# rc2014_8255.net
KiCad netlist of a schematic drawn in EAGLE
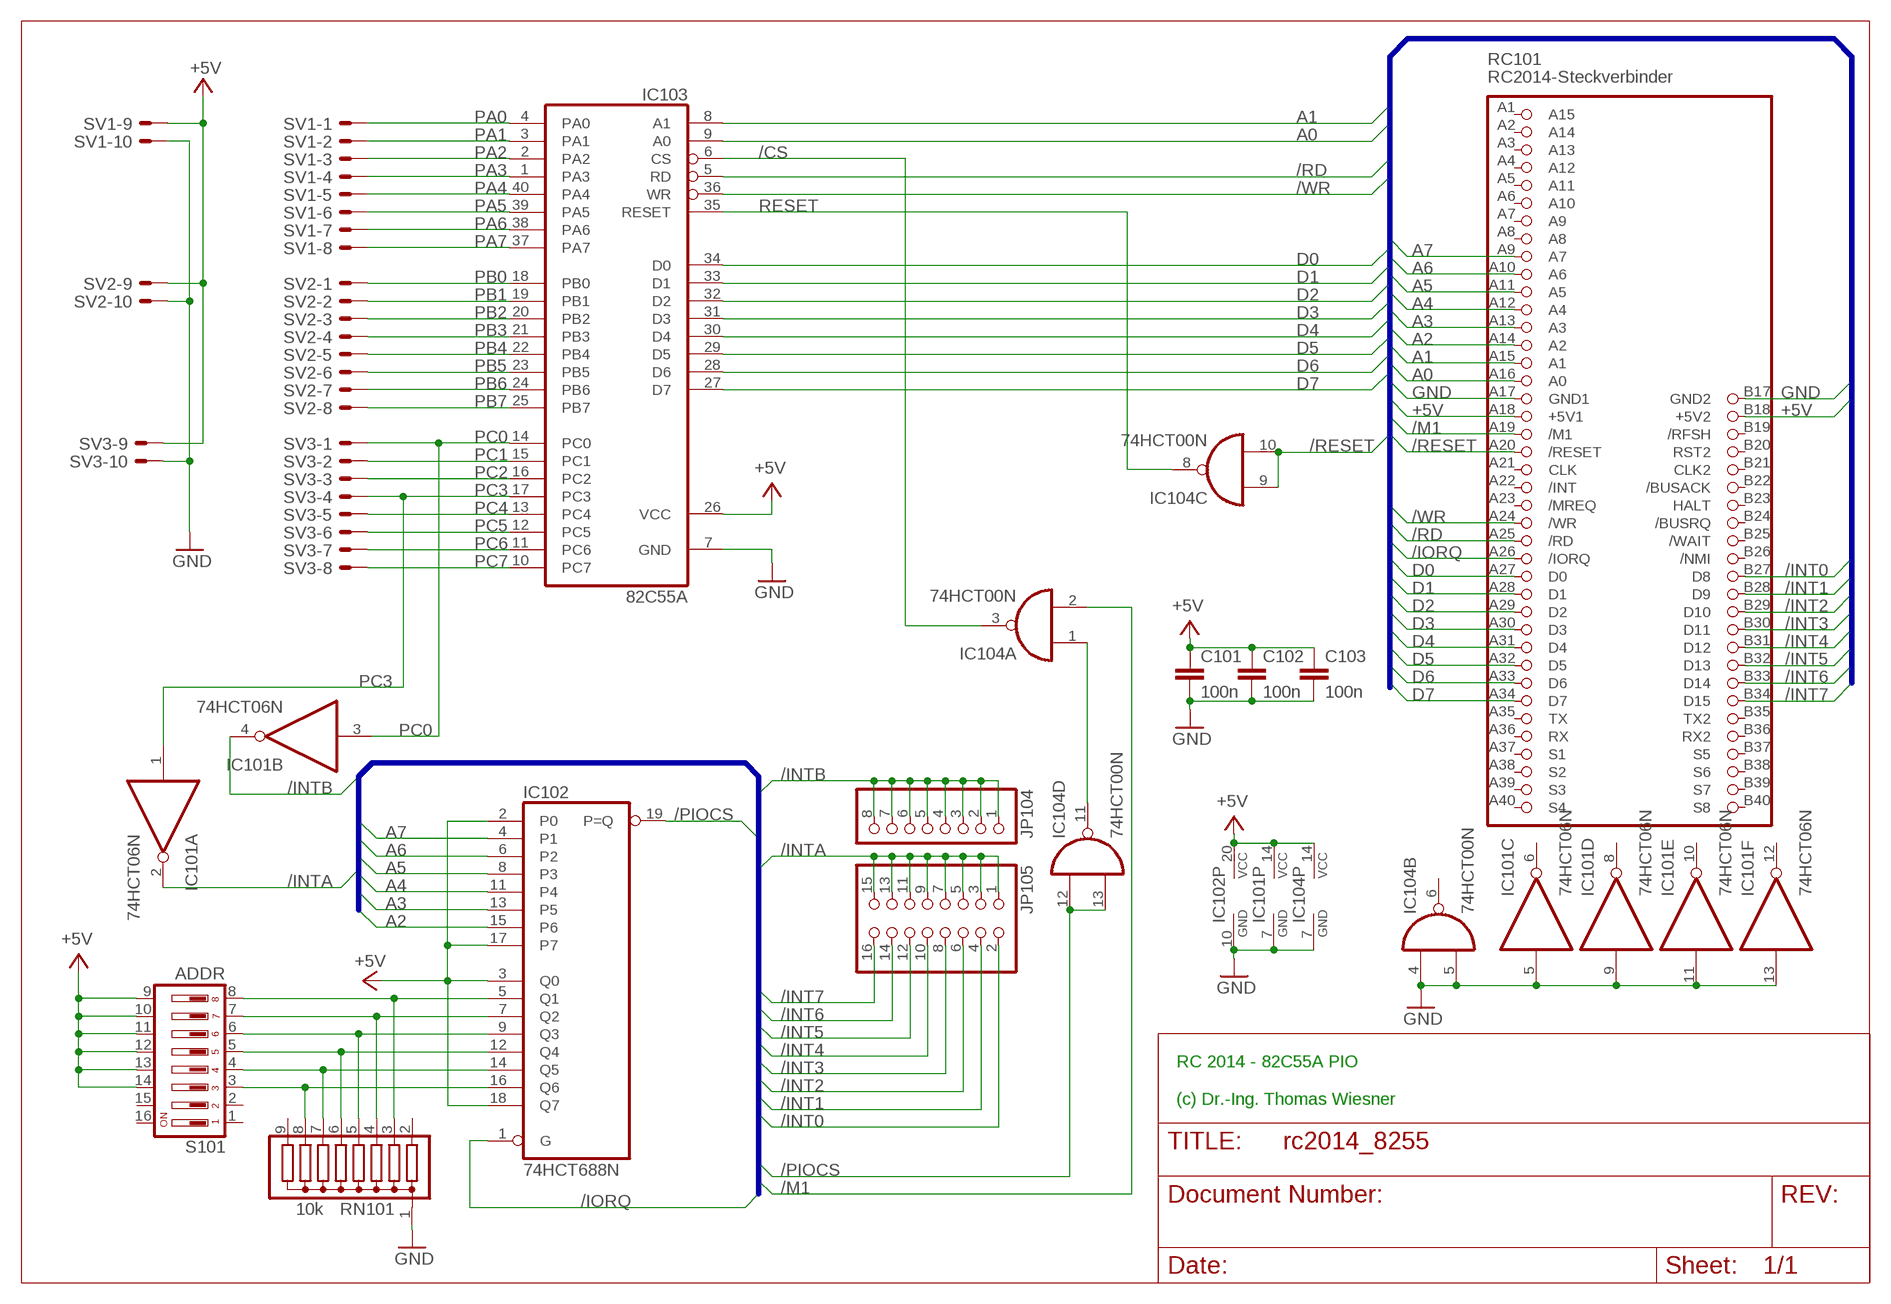
[diagram p0: schematic, sheet 1]

(export (version "E")
  (design (tool "Eeschema 10.0.6"))
  (components
    (comp (ref "C101")
      (value "100n")
      (footprint "eagle-import:C025-025X050")
      (libsource (lib "eagle-import") (part "C-EU025-025X050"))
    )
    (comp (ref "C102")
      (value "100n")
      (footprint "eagle-import:C025-025X050")
      (libsource (lib "eagle-import") (part "C-EU025-025X050"))
    )
    (comp (ref "C103")
      (value "100n")
      (footprint "eagle-import:C025-025X050")
      (libsource (lib "eagle-import") (part "C-EU025-025X050"))
    )
    (comp (ref "IC101")
      (value "74HCT06N")
      (footprint "eagle-import:DIL14")
      (libsource (lib "eagle-import") (part "7406NLS"))
    )
    (comp (ref "IC102")
      (value "74HCT688N")
      (footprint "eagle-import:DIL20")
      (libsource (lib "eagle-import") (part "74688NHCT"))
    )
    (comp (ref "IC103")
      (value "82C55A")
      (footprint "eagle-import:DIL40")
      (fields (field (name "MF") "INTERSIL") (field (name "MPN") "IP82C55AZ"))
      (libsource (lib "eagle-import") (part "82C55A"))
    )
    (comp (ref "IC104")
      (value "74HCT00N")
      (footprint "eagle-import:DIL14")
      (libsource (lib "eagle-import") (part "7400NLS"))
    )
    (comp (ref "JP104")
      (value "PINHD-1X8")
      (footprint "eagle-import:1X08")
      (libsource (lib "eagle-import") (part "PINHD-1X8"))
    )
    (comp (ref "JP105")
      (value "PINHD-2X8")
      (footprint "eagle-import:2X08")
      (libsource (lib "eagle-import") (part "PINHD-2X8"))
    )
    (comp (ref "RC101")
      (value "RC2014-Steckverbinder")
      (footprint "eagle-import:RC2014-STECKER")
      (libsource (lib "eagle-import") (part "RC2014STECKER"))
    )
    (comp (ref "RN101")
      (value "10k")
      (footprint "eagle-import:SIL9")
      (libsource (lib "eagle-import") (part "G08R"))
    )
    (comp (ref "S101")
      (value "ADDR")
      (footprint "eagle-import:DS-08")
      (fields (field (name "MPN") "DS08"))
      (libsource (lib "eagle-import") (part "DS08"))
    )
    (comp (ref "SV1")
      (value "ML10LE")
      (footprint "eagle-import:ML10L")
      (libsource (lib "eagle-import") (part "ML10LE"))
    )
    (comp (ref "SV2")
      (value "ML10LE")
      (footprint "eagle-import:ML10L")
      (libsource (lib "eagle-import") (part "ML10LE"))
    )
    (comp (ref "SV3")
      (value "ML10LE")
      (footprint "eagle-import:ML10L")
      (libsource (lib "eagle-import") (part "ML10LE"))
    )
  )
  (nets
    (net (code "2") (name "+5V") (class "Default")
      (node (ref "C101") (pin "1") (pinfunction "1_1") (pintype "passive"))
      (node (ref "C102") (pin "1") (pinfunction "1_1") (pintype "passive"))
      (node (ref "C103") (pin "1") (pinfunction "1_1") (pintype "passive"))
      (node (ref "IC101") (pin "14") (pinfunction "VCC_14") (pintype "power_in"))
      (node (ref "IC102") (pin "17") (pinfunction "P7_17") (pintype "input"))
      (node (ref "IC102") (pin "18") (pinfunction "Q7_18") (pintype "input"))
      (node (ref "IC102") (pin "2") (pinfunction "P0_2") (pintype "input"))
      (node (ref "IC102") (pin "20") (pinfunction "VCC_20") (pintype "power_in"))
      (node (ref "IC102") (pin "3") (pinfunction "Q0_3") (pintype "input"))
      (node (ref "IC103") (pin "26") (pinfunction "VCC_26") (pintype "power_in"))
      (node (ref "IC104") (pin "14") (pinfunction "VCC_14") (pintype "power_in"))
      (node (ref "RC101") (pin "A18") (pinfunction "+5V1_A18") (pintype "passive"))
      (node (ref "RC101") (pin "B18") (pinfunction "+5V2_B18") (pintype "passive"))
      (node (ref "S101") (pin "10") (pinfunction "10_10") (pintype "passive"))
      (node (ref "S101") (pin "11") (pinfunction "11_11") (pintype "passive"))
      (node (ref "S101") (pin "12") (pinfunction "12_12") (pintype "passive"))
      (node (ref "S101") (pin "13") (pinfunction "13_13") (pintype "passive"))
      (node (ref "S101") (pin "14") (pinfunction "14_14") (pintype "passive"))
      (node (ref "S101") (pin "9") (pinfunction "9_9") (pintype "passive"))
      (node (ref "SV1") (pin "9") (pinfunction "S_9") (pintype "passive"))
      (node (ref "SV2") (pin "9") (pinfunction "S_9") (pintype "passive"))
      (node (ref "SV3") (pin "9") (pinfunction "S_9") (pintype "passive"))
    )
    (net (code "4") (name "A0") (class "Default")
      (node (ref "IC103") (pin "9") (pinfunction "A0_9") (pintype "input"))
      (node (ref "RC101") (pin "A16") (pinfunction "A0_A16") (pintype "passive"))
    )
    (net (code "5") (name "A1") (class "Default")
      (node (ref "IC103") (pin "8") (pinfunction "A1_8") (pintype "input"))
      (node (ref "RC101") (pin "A15") (pinfunction "A1_A15") (pintype "passive"))
    )
    (net (code "6") (name "A2") (class "Default")
      (node (ref "IC102") (pin "15") (pinfunction "P6_15") (pintype "input"))
      (node (ref "RC101") (pin "A14") (pinfunction "A2_A14") (pintype "passive"))
    )
    (net (code "7") (name "A3") (class "Default")
      (node (ref "IC102") (pin "13") (pinfunction "P5_13") (pintype "input"))
      (node (ref "RC101") (pin "A13") (pinfunction "A3_A13") (pintype "passive"))
    )
    (net (code "8") (name "A4") (class "Default")
      (node (ref "IC102") (pin "11") (pinfunction "P4_11") (pintype "input"))
      (node (ref "RC101") (pin "A12") (pinfunction "A4_A12") (pintype "passive"))
    )
    (net (code "9") (name "A5") (class "Default")
      (node (ref "IC102") (pin "8") (pinfunction "P3_8") (pintype "input"))
      (node (ref "RC101") (pin "A11") (pinfunction "A5_A11") (pintype "passive"))
    )
    (net (code "10") (name "A6") (class "Default")
      (node (ref "IC102") (pin "6") (pinfunction "P2_6") (pintype "input"))
      (node (ref "RC101") (pin "A10") (pinfunction "A6_A10") (pintype "passive"))
    )
    (net (code "11") (name "A7") (class "Default")
      (node (ref "IC102") (pin "4") (pinfunction "P1_4") (pintype "input"))
      (node (ref "RC101") (pin "A9") (pinfunction "A7_A9") (pintype "passive"))
    )
    (net (code "12") (name "D0") (class "Default")
      (node (ref "IC103") (pin "34") (pinfunction "D0_34") (pintype "bidirectional"))
      (node (ref "RC101") (pin "A27") (pinfunction "D0_A27") (pintype "passive"))
    )
    (net (code "13") (name "D1") (class "Default")
      (node (ref "IC103") (pin "33") (pinfunction "D1_33") (pintype "bidirectional"))
      (node (ref "RC101") (pin "A28") (pinfunction "D1_A28") (pintype "passive"))
    )
    (net (code "14") (name "D2") (class "Default")
      (node (ref "IC103") (pin "32") (pinfunction "D2_32") (pintype "bidirectional"))
      (node (ref "RC101") (pin "A29") (pinfunction "D2_A29") (pintype "passive"))
    )
    (net (code "15") (name "D3") (class "Default")
      (node (ref "IC103") (pin "31") (pinfunction "D3_31") (pintype "bidirectional"))
      (node (ref "RC101") (pin "A30") (pinfunction "D3_A30") (pintype "passive"))
    )
    (net (code "16") (name "D4") (class "Default")
      (node (ref "IC103") (pin "30") (pinfunction "D4_30") (pintype "bidirectional"))
      (node (ref "RC101") (pin "A31") (pinfunction "D4_A31") (pintype "passive"))
    )
    (net (code "17") (name "D5") (class "Default")
      (node (ref "IC103") (pin "29") (pinfunction "D5_29") (pintype "bidirectional"))
      (node (ref "RC101") (pin "A32") (pinfunction "D5_A32") (pintype "passive"))
    )
    (net (code "18") (name "D6") (class "Default")
      (node (ref "IC103") (pin "28") (pinfunction "D6_28") (pintype "bidirectional"))
      (node (ref "RC101") (pin "A33") (pinfunction "D6_A33") (pintype "passive"))
    )
    (net (code "19") (name "D7") (class "Default")
      (node (ref "IC103") (pin "27") (pinfunction "D7_27") (pintype "bidirectional"))
      (node (ref "RC101") (pin "A34") (pinfunction "D7_A34") (pintype "passive"))
    )
    (net (code "20") (name "GND") (class "Default")
      (node (ref "C101") (pin "2") (pinfunction "2_2") (pintype "passive"))
      (node (ref "C102") (pin "2") (pinfunction "2_2") (pintype "passive"))
      (node (ref "C103") (pin "2") (pinfunction "2_2") (pintype "passive"))
      (node (ref "IC101") (pin "11") (pinfunction "I_11") (pintype "input"))
      (node (ref "IC101") (pin "13") (pinfunction "I_13") (pintype "input"))
      (node (ref "IC101") (pin "5") (pinfunction "I_5") (pintype "input"))
      (node (ref "IC101") (pin "7") (pinfunction "GND_7") (pintype "power_in"))
      (node (ref "IC101") (pin "9") (pinfunction "I_9") (pintype "input"))
      (node (ref "IC102") (pin "10") (pinfunction "GND_10") (pintype "power_in"))
      (node (ref "IC103") (pin "7") (pinfunction "GND_7") (pintype "power_in"))
      (node (ref "IC104") (pin "4") (pinfunction "I0_4") (pintype "input"))
      (node (ref "IC104") (pin "5") (pinfunction "I1_5") (pintype "input"))
      (node (ref "IC104") (pin "7") (pinfunction "GND_7") (pintype "power_in"))
      (node (ref "RC101") (pin "A17") (pinfunction "GND1_A17") (pintype "passive"))
      (node (ref "RC101") (pin "B17") (pinfunction "GND2_B17") (pintype "passive"))
      (node (ref "RN101") (pin "1") (pinfunction "1_1") (pintype "passive"))
      (node (ref "SV1") (pin "10") (pinfunction "S_10") (pintype "passive"))
      (node (ref "SV2") (pin "10") (pinfunction "S_10") (pintype "passive"))
      (node (ref "SV3") (pin "10") (pinfunction "S_10") (pintype "passive"))
    )
    (net (code "21") (name "Net-(IC102A-Q1)") (class "Default")
      (node (ref "IC102") (pin "5") (pinfunction "Q1_5") (pintype "input"))
      (node (ref "RN101") (pin "3") (pinfunction "3_3") (pintype "passive"))
      (node (ref "S101") (pin "8") (pinfunction "8_8") (pintype "passive"))
    )
    (net (code "22") (name "Net-(IC102A-Q2)") (class "Default")
      (node (ref "IC102") (pin "7") (pinfunction "Q2_7") (pintype "input"))
      (node (ref "RN101") (pin "4") (pinfunction "4_4") (pintype "passive"))
      (node (ref "S101") (pin "7") (pinfunction "7_7") (pintype "passive"))
    )
    (net (code "23") (name "Net-(IC102A-Q3)") (class "Default")
      (node (ref "IC102") (pin "9") (pinfunction "Q3_9") (pintype "input"))
      (node (ref "RN101") (pin "5") (pinfunction "5_5") (pintype "passive"))
      (node (ref "S101") (pin "6") (pinfunction "6_6") (pintype "passive"))
    )
    (net (code "24") (name "Net-(IC102A-Q4)") (class "Default")
      (node (ref "IC102") (pin "12") (pinfunction "Q4_12") (pintype "input"))
      (node (ref "RN101") (pin "6") (pinfunction "6_6") (pintype "passive"))
      (node (ref "S101") (pin "5") (pinfunction "5_5") (pintype "passive"))
    )
    (net (code "25") (name "Net-(IC102A-Q5)") (class "Default")
      (node (ref "IC102") (pin "14") (pinfunction "Q5_14") (pintype "input"))
      (node (ref "RN101") (pin "7") (pinfunction "7_7") (pintype "passive"))
      (node (ref "S101") (pin "4") (pinfunction "4_4") (pintype "passive"))
    )
    (net (code "26") (name "Net-(IC102A-Q6)") (class "Default")
      (node (ref "IC102") (pin "16") (pinfunction "Q6_16") (pintype "input"))
      (node (ref "RN101") (pin "8") (pinfunction "8_8") (pintype "passive"))
      (node (ref "S101") (pin "3") (pinfunction "3_3") (pintype "passive"))
    )
    (net (code "27") (name "Net-(IC104A-I0)") (class "Default")
      (node (ref "IC104") (pin "1") (pinfunction "I0_1") (pintype "input"))
      (node (ref "IC104") (pin "11") (pinfunction "O_11") (pintype "output"))
    )
    (net (code "28") (name "PA0") (class "Default")
      (node (ref "IC103") (pin "4") (pinfunction "PA0_4") (pintype "bidirectional"))
      (node (ref "SV1") (pin "1") (pinfunction "S_1") (pintype "passive"))
    )
    (net (code "29") (name "PA1") (class "Default")
      (node (ref "IC103") (pin "3") (pinfunction "PA1_3") (pintype "bidirectional"))
      (node (ref "SV1") (pin "2") (pinfunction "S_2") (pintype "passive"))
    )
    (net (code "30") (name "PA2") (class "Default")
      (node (ref "IC103") (pin "2") (pinfunction "PA2_2") (pintype "bidirectional"))
      (node (ref "SV1") (pin "3") (pinfunction "S_3") (pintype "passive"))
    )
    (net (code "31") (name "PA3") (class "Default")
      (node (ref "IC103") (pin "1") (pinfunction "PA3_1") (pintype "bidirectional"))
      (node (ref "SV1") (pin "4") (pinfunction "S_4") (pintype "passive"))
    )
    (net (code "32") (name "PA4") (class "Default")
      (node (ref "IC103") (pin "40") (pinfunction "PA4_40") (pintype "bidirectional"))
      (node (ref "SV1") (pin "5") (pinfunction "S_5") (pintype "passive"))
    )
    (net (code "33") (name "PA5") (class "Default")
      (node (ref "IC103") (pin "39") (pinfunction "PA5_39") (pintype "bidirectional"))
      (node (ref "SV1") (pin "6") (pinfunction "S_6") (pintype "passive"))
    )
    (net (code "34") (name "PA6") (class "Default")
      (node (ref "IC103") (pin "38") (pinfunction "PA6_38") (pintype "bidirectional"))
      (node (ref "SV1") (pin "7") (pinfunction "S_7") (pintype "passive"))
    )
    (net (code "35") (name "PA7") (class "Default")
      (node (ref "IC103") (pin "37") (pinfunction "PA7_37") (pintype "bidirectional"))
      (node (ref "SV1") (pin "8") (pinfunction "S_8") (pintype "passive"))
    )
    (net (code "36") (name "PB0") (class "Default")
      (node (ref "IC103") (pin "18") (pinfunction "PB0_18") (pintype "bidirectional"))
      (node (ref "SV2") (pin "1") (pinfunction "S_1") (pintype "passive"))
    )
    (net (code "37") (name "PB1") (class "Default")
      (node (ref "IC103") (pin "19") (pinfunction "PB1_19") (pintype "bidirectional"))
      (node (ref "SV2") (pin "2") (pinfunction "S_2") (pintype "passive"))
    )
    (net (code "38") (name "PB2") (class "Default")
      (node (ref "IC103") (pin "20") (pinfunction "PB2_20") (pintype "bidirectional"))
      (node (ref "SV2") (pin "3") (pinfunction "S_3") (pintype "passive"))
    )
    (net (code "39") (name "PB3") (class "Default")
      (node (ref "IC103") (pin "21") (pinfunction "PB3_21") (pintype "bidirectional"))
      (node (ref "SV2") (pin "4") (pinfunction "S_4") (pintype "passive"))
    )
    (net (code "40") (name "PB4") (class "Default")
      (node (ref "IC103") (pin "22") (pinfunction "PB4_22") (pintype "bidirectional"))
      (node (ref "SV2") (pin "5") (pinfunction "S_5") (pintype "passive"))
    )
    (net (code "41") (name "PB5") (class "Default")
      (node (ref "IC103") (pin "23") (pinfunction "PB5_23") (pintype "bidirectional"))
      (node (ref "SV2") (pin "6") (pinfunction "S_6") (pintype "passive"))
    )
    (net (code "42") (name "PB6") (class "Default")
      (node (ref "IC103") (pin "24") (pinfunction "PB6_24") (pintype "bidirectional"))
      (node (ref "SV2") (pin "7") (pinfunction "S_7") (pintype "passive"))
    )
    (net (code "43") (name "PB7") (class "Default")
      (node (ref "IC103") (pin "25") (pinfunction "PB7_25") (pintype "bidirectional"))
      (node (ref "SV2") (pin "8") (pinfunction "S_8") (pintype "passive"))
    )
    (net (code "44") (name "PC0") (class "Default")
      (node (ref "IC101") (pin "3") (pinfunction "I_3") (pintype "input"))
      (node (ref "IC103") (pin "14") (pinfunction "PC0_14") (pintype "bidirectional"))
      (node (ref "SV3") (pin "1") (pinfunction "S_1") (pintype "passive"))
    )
    (net (code "45") (name "PC1") (class "Default")
      (node (ref "IC103") (pin "15") (pinfunction "PC1_15") (pintype "bidirectional"))
      (node (ref "SV3") (pin "2") (pinfunction "S_2") (pintype "passive"))
    )
    (net (code "46") (name "PC2") (class "Default")
      (node (ref "IC103") (pin "16") (pinfunction "PC2_16") (pintype "bidirectional"))
      (node (ref "SV3") (pin "3") (pinfunction "S_3") (pintype "passive"))
    )
    (net (code "47") (name "PC3") (class "Default")
      (node (ref "IC101") (pin "1") (pinfunction "I_1") (pintype "input"))
      (node (ref "IC103") (pin "17") (pinfunction "PC3_17") (pintype "bidirectional"))
      (node (ref "SV3") (pin "4") (pinfunction "S_4") (pintype "passive"))
    )
    (net (code "48") (name "PC4") (class "Default")
      (node (ref "IC103") (pin "13") (pinfunction "PC4_13") (pintype "bidirectional"))
      (node (ref "SV3") (pin "5") (pinfunction "S_5") (pintype "passive"))
    )
    (net (code "49") (name "PC5") (class "Default")
      (node (ref "IC103") (pin "12") (pinfunction "PC5_12") (pintype "bidirectional"))
      (node (ref "SV3") (pin "6") (pinfunction "S_6") (pintype "passive"))
    )
    (net (code "50") (name "PC6") (class "Default")
      (node (ref "IC103") (pin "11") (pinfunction "PC6_11") (pintype "bidirectional"))
      (node (ref "SV3") (pin "7") (pinfunction "S_7") (pintype "passive"))
    )
    (net (code "51") (name "PC7") (class "Default")
      (node (ref "IC103") (pin "10") (pinfunction "PC7_10") (pintype "bidirectional"))
      (node (ref "SV3") (pin "8") (pinfunction "S_8") (pintype "passive"))
    )
    (net (code "52") (name "RESET") (class "Default")
      (node (ref "IC103") (pin "35") (pinfunction "RESET_35") (pintype "input"))
      (node (ref "IC104") (pin "8") (pinfunction "O_8") (pintype "output"))
    )
    (net (code "53") (name "unconnected-(IC101C-O-Pad6)") (class "Default")
      (node (ref "IC101") (pin "6") (pinfunction "O_6") (pintype "open_collector"))
    )
    (net (code "54") (name "unconnected-(IC101D-O-Pad8)") (class "Default")
      (node (ref "IC101") (pin "8") (pinfunction "O_8") (pintype "open_collector"))
    )
    (net (code "55") (name "unconnected-(IC101E-O-Pad10)") (class "Default")
      (node (ref "IC101") (pin "10") (pinfunction "O_10") (pintype "open_collector"))
    )
    (net (code "56") (name "unconnected-(IC101F-O-Pad12)") (class "Default")
      (node (ref "IC101") (pin "12") (pinfunction "O_12") (pintype "open_collector"))
    )
    (net (code "57") (name "unconnected-(IC104B-O-Pad6)") (class "Default")
      (node (ref "IC104") (pin "6") (pinfunction "O_6") (pintype "output"))
    )
    (net (code "58") (name "unconnected-(RC101-A9-PadA7)") (class "Default")
      (node (ref "RC101") (pin "A7") (pinfunction "A9_A7") (pintype "passive"))
    )
    (net (code "59") (name "unconnected-(RC101-A10-PadA6)") (class "Default")
      (node (ref "RC101") (pin "A6") (pinfunction "A10_A6") (pintype "passive"))
    )
    (net (code "60") (name "unconnected-(RC101-A11-PadA5)") (class "Default")
      (node (ref "RC101") (pin "A5") (pinfunction "A11_A5") (pintype "passive"))
    )
    (net (code "61") (name "unconnected-(RC101-A12-PadA4)") (class "Default")
      (node (ref "RC101") (pin "A4") (pinfunction "A12_A4") (pintype "passive"))
    )
    (net (code "62") (name "unconnected-(RC101-A13-PadA3)") (class "Default")
      (node (ref "RC101") (pin "A3") (pinfunction "A13_A3") (pintype "passive"))
    )
    (net (code "63") (name "unconnected-(RC101-A14-PadA2)") (class "Default")
      (node (ref "RC101") (pin "A2") (pinfunction "A14_A2") (pintype "passive"))
    )
    (net (code "64") (name "unconnected-(RC101-A15-PadA1)") (class "Default")
      (node (ref "RC101") (pin "A1") (pinfunction "A15_A1") (pintype "passive"))
    )
    (net (code "65") (name "unconnected-(RC101-CLK-PadA21)") (class "Default")
      (node (ref "RC101") (pin "A21") (pinfunction "CLK_A21") (pintype "passive"))
    )
    (net (code "66") (name "unconnected-(RC101-CLK2-PadB21)") (class "Default")
      (node (ref "RC101") (pin "B21") (pinfunction "CLK2_B21") (pintype "passive"))
    )
    (net (code "67") (name "unconnected-(RC101-HALT-PadB23)") (class "Default")
      (node (ref "RC101") (pin "B23") (pinfunction "HALT_B23") (pintype "passive"))
    )
    (net (code "68") (name "unconnected-(RC101-PadA8)") (class "Default")
      (node (ref "RC101") (pin "A8") (pinfunction "A8_A8") (pintype "passive"))
    )
    (net (code "69") (name "unconnected-(RC101-RST2-PadB20)") (class "Default")
      (node (ref "RC101") (pin "B20") (pinfunction "RST2_B20") (pintype "passive"))
    )
    (net (code "70") (name "unconnected-(RC101-RX-PadA36)") (class "Default")
      (node (ref "RC101") (pin "A36") (pinfunction "RX_A36") (pintype "passive"))
    )
    (net (code "71") (name "unconnected-(RC101-RX2-PadB36)") (class "Default")
      (node (ref "RC101") (pin "B36") (pinfunction "RX2_B36") (pintype "passive"))
    )
    (net (code "72") (name "unconnected-(RC101-S1-PadA37)") (class "Default")
      (node (ref "RC101") (pin "A37") (pinfunction "S1_A37") (pintype "passive"))
    )
    (net (code "73") (name "unconnected-(RC101-S2-PadA38)") (class "Default")
      (node (ref "RC101") (pin "A38") (pinfunction "S2_A38") (pintype "passive"))
    )
    (net (code "74") (name "unconnected-(RC101-S3-PadA39)") (class "Default")
      (node (ref "RC101") (pin "A39") (pinfunction "S3_A39") (pintype "passive"))
    )
    (net (code "75") (name "unconnected-(RC101-S4-PadA40)") (class "Default")
      (node (ref "RC101") (pin "A40") (pinfunction "S4_A40") (pintype "passive"))
    )
    (net (code "76") (name "unconnected-(RC101-S5-PadB37)") (class "Default")
      (node (ref "RC101") (pin "B37") (pinfunction "S5_B37") (pintype "passive"))
    )
    (net (code "77") (name "unconnected-(RC101-S6-PadB38)") (class "Default")
      (node (ref "RC101") (pin "B38") (pinfunction "S6_B38") (pintype "passive"))
    )
    (net (code "78") (name "unconnected-(RC101-S7-PadB39)") (class "Default")
      (node (ref "RC101") (pin "B39") (pinfunction "S7_B39") (pintype "passive"))
    )
    (net (code "79") (name "unconnected-(RC101-S8-PadB40)") (class "Default")
      (node (ref "RC101") (pin "B40") (pinfunction "S8_B40") (pintype "passive"))
    )
    (net (code "80") (name "unconnected-(RC101-TX-PadA35)") (class "Default")
      (node (ref "RC101") (pin "A35") (pinfunction "TX_A35") (pintype "passive"))
    )
    (net (code "81") (name "unconnected-(RC101-TX2-PadB35)") (class "Default")
      (node (ref "RC101") (pin "B35") (pinfunction "TX2_B35") (pintype "passive"))
    )
    (net (code "82") (name "unconnected-(RC101-{slash}BUSACK-PadB22)") (class "Default")
      (node (ref "RC101") (pin "B22") (pinfunction "/BUSACK_B22") (pintype "passive"))
    )
    (net (code "83") (name "unconnected-(RC101-{slash}BUSRQ-PadB24)") (class "Default")
      (node (ref "RC101") (pin "B24") (pinfunction "/BUSRQ_B24") (pintype "passive"))
    )
    (net (code "84") (name "unconnected-(RC101-{slash}INT-PadA22)") (class "Default")
      (node (ref "RC101") (pin "A22") (pinfunction "/INT_A22") (pintype "passive"))
    )
    (net (code "85") (name "unconnected-(RC101-{slash}MREQ-PadA23)") (class "Default")
      (node (ref "RC101") (pin "A23") (pinfunction "/MREQ_A23") (pintype "passive"))
    )
    (net (code "86") (name "unconnected-(RC101-{slash}NMI-PadB26)") (class "Default")
      (node (ref "RC101") (pin "B26") (pinfunction "/NMI_B26") (pintype "passive"))
    )
    (net (code "87") (name "unconnected-(RC101-{slash}RFSH-PadB19)") (class "Default")
      (node (ref "RC101") (pin "B19") (pinfunction "/RFSH_B19") (pintype "passive"))
    )
    (net (code "88") (name "unconnected-(RC101-{slash}WAIT-PadB25)") (class "Default")
      (node (ref "RC101") (pin "B25") (pinfunction "/WAIT_B25") (pintype "passive"))
    )
    (net (code "89") (name "unconnected-(RN101-Pad2)") (class "Default")
      (node (ref "RN101") (pin "2") (pinfunction "2_2") (pintype "passive"))
    )
    (net (code "90") (name "unconnected-(RN101-Pad9)") (class "Default")
      (node (ref "RN101") (pin "9") (pinfunction "9_9") (pintype "passive"))
    )
    (net (code "91") (name "unconnected-(S101-Pad1)") (class "Default")
      (node (ref "S101") (pin "1") (pinfunction "1_1") (pintype "passive"))
    )
    (net (code "92") (name "unconnected-(S101-Pad2)") (class "Default")
      (node (ref "S101") (pin "2") (pinfunction "2_2") (pintype "passive"))
    )
    (net (code "93") (name "unconnected-(S101-Pad15)") (class "Default")
      (node (ref "S101") (pin "15") (pinfunction "15_15") (pintype "passive"))
    )
    (net (code "94") (name "unconnected-(S101-Pad16)") (class "Default")
      (node (ref "S101") (pin "16") (pinfunction "16_16") (pintype "passive"))
    )
    (net (code "95") (name "{slash}CS") (class "Default")
      (node (ref "IC103") (pin "6") (pinfunction "CS_6") (pintype "input"))
      (node (ref "IC104") (pin "3") (pinfunction "O_3") (pintype "output"))
    )
    (net (code "96") (name "{slash}INT0") (class "Default")
      (node (ref "JP105") (pin "2") (pinfunction "2_2") (pintype "passive"))
      (node (ref "RC101") (pin "B27") (pinfunction "D8_B27") (pintype "passive"))
    )
    (net (code "97") (name "{slash}INT1") (class "Default")
      (node (ref "JP105") (pin "4") (pinfunction "4_4") (pintype "passive"))
      (node (ref "RC101") (pin "B28") (pinfunction "D9_B28") (pintype "passive"))
    )
    (net (code "98") (name "{slash}INT2") (class "Default")
      (node (ref "JP105") (pin "6") (pinfunction "6_6") (pintype "passive"))
      (node (ref "RC101") (pin "B29") (pinfunction "D10_B29") (pintype "passive"))
    )
    (net (code "99") (name "{slash}INT3") (class "Default")
      (node (ref "JP105") (pin "8") (pinfunction "8_8") (pintype "passive"))
      (node (ref "RC101") (pin "B30") (pinfunction "D11_B30") (pintype "passive"))
    )
    (net (code "100") (name "{slash}INT4") (class "Default")
      (node (ref "JP105") (pin "10") (pinfunction "10_10") (pintype "passive"))
      (node (ref "RC101") (pin "B31") (pinfunction "D12_B31") (pintype "passive"))
    )
    (net (code "101") (name "{slash}INT5") (class "Default")
      (node (ref "JP105") (pin "12") (pinfunction "12_12") (pintype "passive"))
      (node (ref "RC101") (pin "B32") (pinfunction "D13_B32") (pintype "passive"))
    )
    (net (code "102") (name "{slash}INT6") (class "Default")
      (node (ref "JP105") (pin "14") (pinfunction "14_14") (pintype "passive"))
      (node (ref "RC101") (pin "B33") (pinfunction "D14_B33") (pintype "passive"))
    )
    (net (code "103") (name "{slash}INT7") (class "Default")
      (node (ref "JP105") (pin "16") (pinfunction "16_16") (pintype "passive"))
      (node (ref "RC101") (pin "B34") (pinfunction "D15_B34") (pintype "passive"))
    )
    (net (code "104") (name "{slash}INTA") (class "Default")
      (node (ref "IC101") (pin "2") (pinfunction "O_2") (pintype "open_collector"))
      (node (ref "JP105") (pin "1") (pinfunction "1_1") (pintype "passive"))
      (node (ref "JP105") (pin "11") (pinfunction "11_11") (pintype "passive"))
      (node (ref "JP105") (pin "13") (pinfunction "13_13") (pintype "passive"))
      (node (ref "JP105") (pin "15") (pinfunction "15_15") (pintype "passive"))
      (node (ref "JP105") (pin "3") (pinfunction "3_3") (pintype "passive"))
      (node (ref "JP105") (pin "5") (pinfunction "5_5") (pintype "passive"))
      (node (ref "JP105") (pin "7") (pinfunction "7_7") (pintype "passive"))
      (node (ref "JP105") (pin "9") (pinfunction "9_9") (pintype "passive"))
    )
    (net (code "105") (name "{slash}INTB") (class "Default")
      (node (ref "IC101") (pin "4") (pinfunction "O_4") (pintype "open_collector"))
      (node (ref "JP104") (pin "1") (pinfunction "1_1") (pintype "passive"))
      (node (ref "JP104") (pin "2") (pinfunction "2_2") (pintype "passive"))
      (node (ref "JP104") (pin "3") (pinfunction "3_3") (pintype "passive"))
      (node (ref "JP104") (pin "4") (pinfunction "4_4") (pintype "passive"))
      (node (ref "JP104") (pin "5") (pinfunction "5_5") (pintype "passive"))
      (node (ref "JP104") (pin "6") (pinfunction "6_6") (pintype "passive"))
      (node (ref "JP104") (pin "7") (pinfunction "7_7") (pintype "passive"))
      (node (ref "JP104") (pin "8") (pinfunction "8_8") (pintype "passive"))
    )
    (net (code "106") (name "{slash}IORQ") (class "Default")
      (node (ref "IC102") (pin "1") (pinfunction "G_1") (pintype "input"))
      (node (ref "RC101") (pin "A26") (pinfunction "/IORQ_A26") (pintype "passive"))
    )
    (net (code "107") (name "{slash}M1") (class "Default")
      (node (ref "IC104") (pin "2") (pinfunction "I1_2") (pintype "input"))
      (node (ref "RC101") (pin "A19") (pinfunction "/M1_A19") (pintype "passive"))
    )
    (net (code "108") (name "{slash}PIOCS") (class "Default")
      (node (ref "IC102") (pin "19") (pinfunction "P=Q_19") (pintype "output"))
      (node (ref "IC104") (pin "12") (pinfunction "I0_12") (pintype "input"))
      (node (ref "IC104") (pin "13") (pinfunction "I1_13") (pintype "input"))
    )
    (net (code "109") (name "{slash}RD") (class "Default")
      (node (ref "IC103") (pin "5") (pinfunction "RD_5") (pintype "input"))
      (node (ref "RC101") (pin "A25") (pinfunction "/RD_A25") (pintype "passive"))
    )
    (net (code "110") (name "{slash}RESET") (class "Default")
      (node (ref "IC104") (pin "10") (pinfunction "I1_10") (pintype "input"))
      (node (ref "IC104") (pin "9") (pinfunction "I0_9") (pintype "input"))
      (node (ref "RC101") (pin "A20") (pinfunction "/RESET_A20") (pintype "passive"))
    )
    (net (code "111") (name "{slash}WR") (class "Default")
      (node (ref "IC103") (pin "36") (pinfunction "WR_36") (pintype "input"))
      (node (ref "RC101") (pin "A24") (pinfunction "/WR_A24") (pintype "passive"))
    )
  )
)
